# FPGA_POWER_DGND.net
KiCad netlist of a schematic drawn in Altium Designer
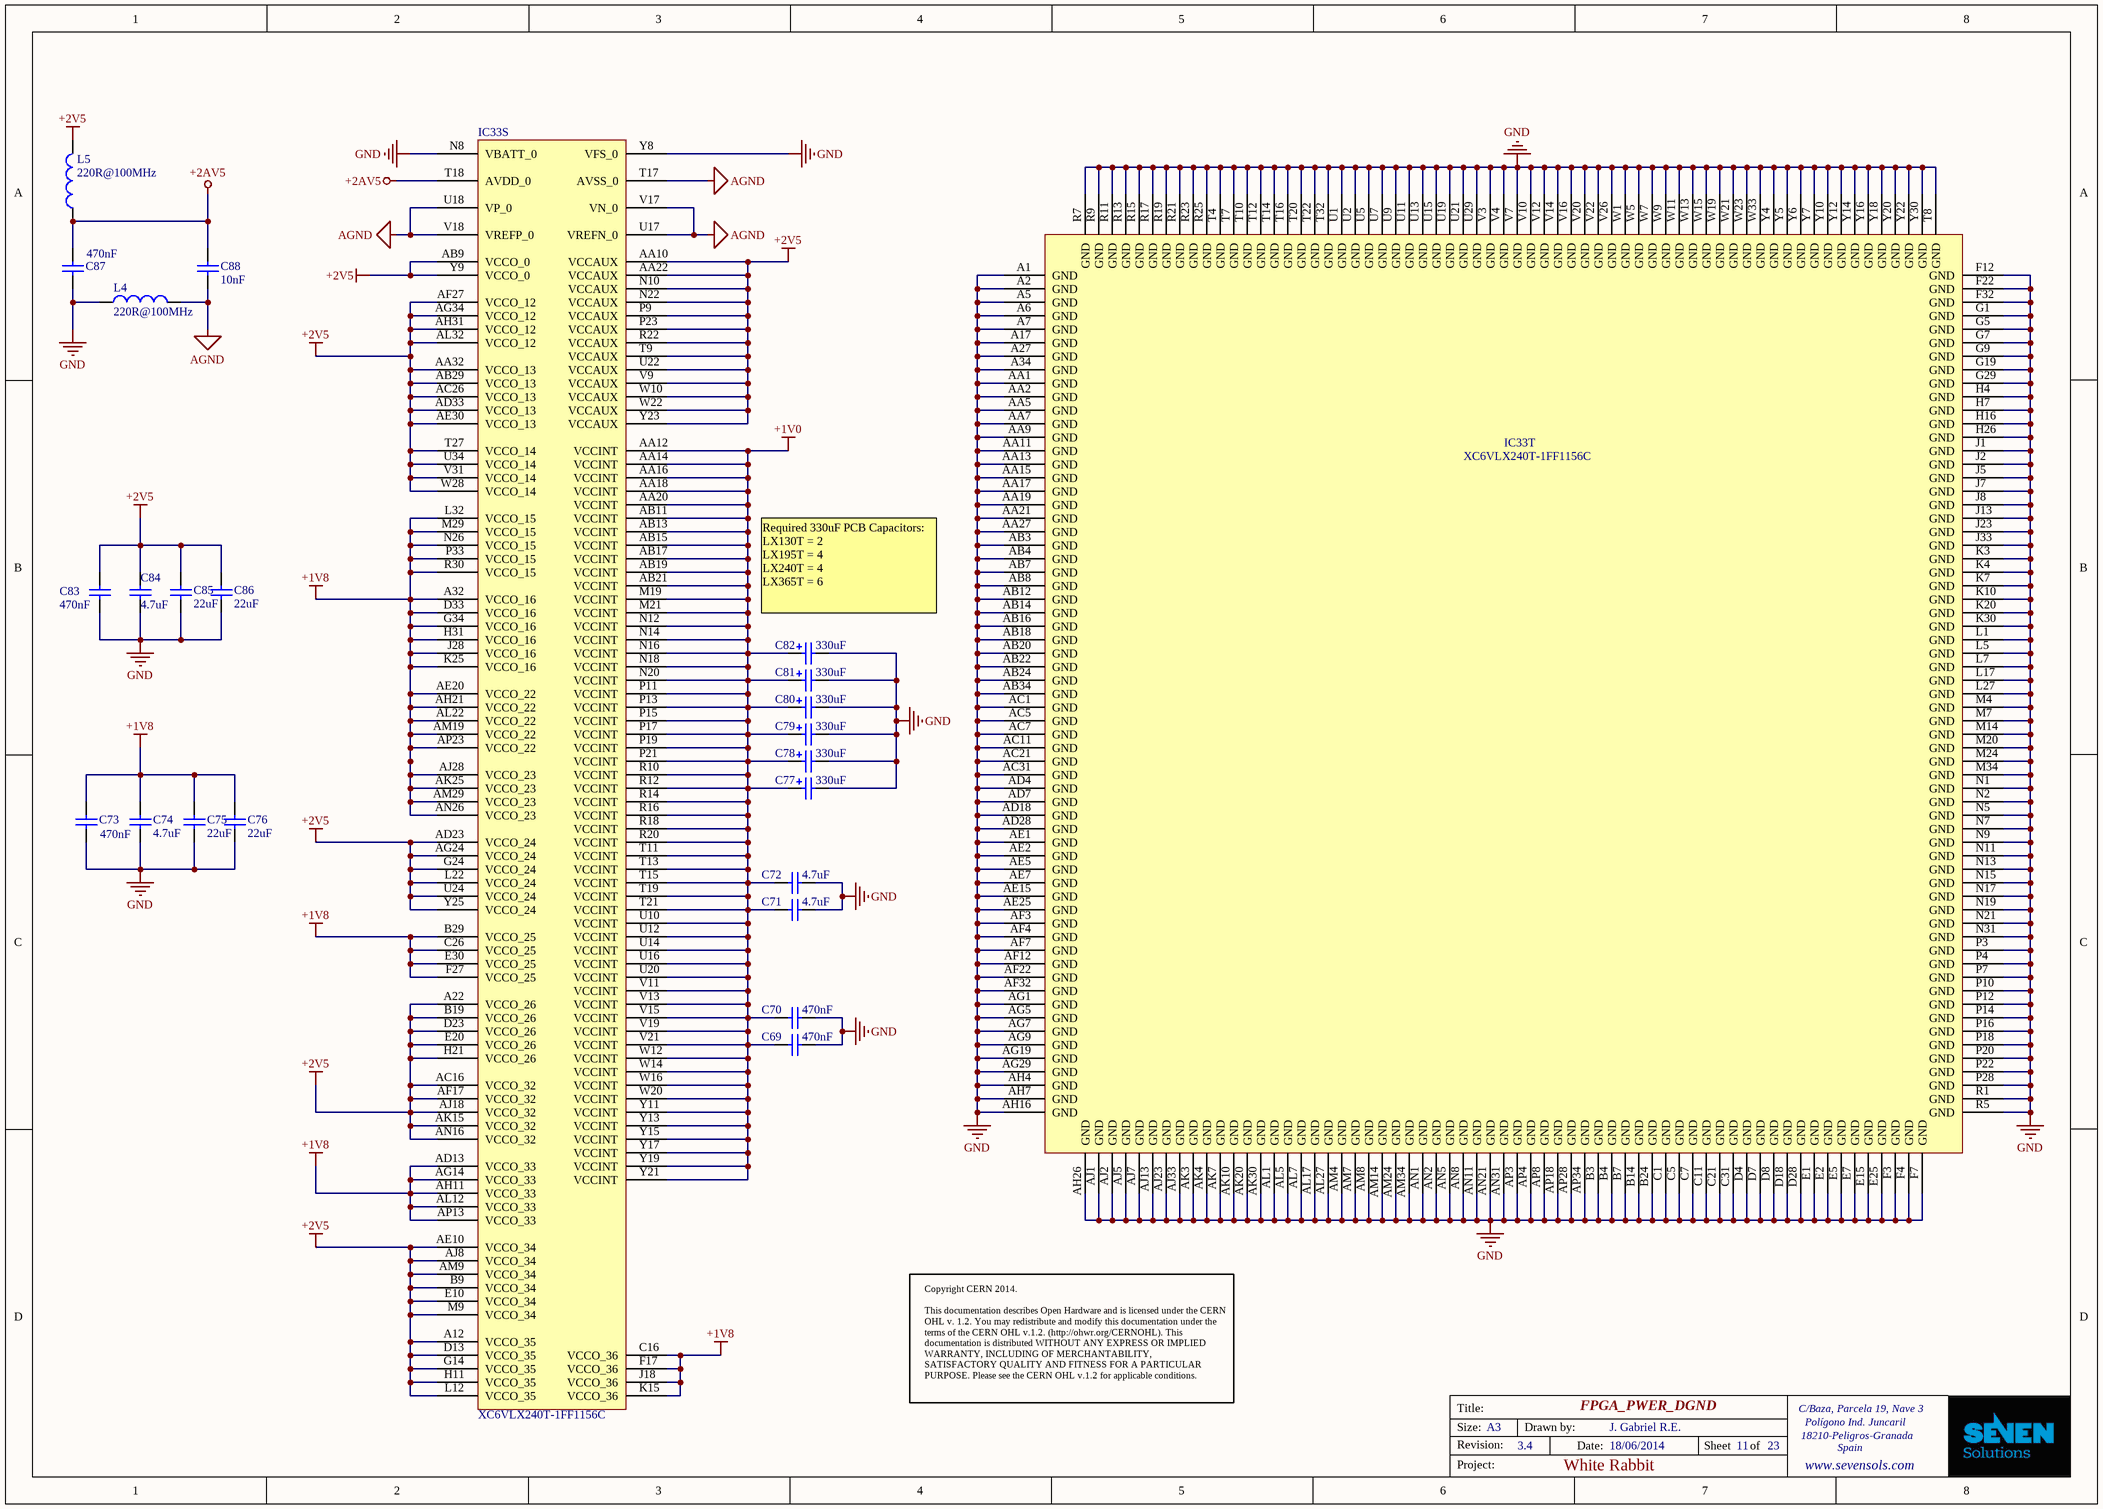
[diagram p0: FPGA_POWER_DGND.SchDoc]

(export (version "E")
  (design (tool "Eeschema 10.0.6"))
  (components
    (comp (ref "C69")
      (value "470nF")
      (footprint "CC1005-0402")
      (description "Capacitor")
      (fields
        (field (name "TOLERANCE") "±10%")
        (field (name "VOLTAGE") "16V")
        (field (name "PUBLISHER") "Altium Limited")
      )
      (libsource (lib "wr_switch") (part "Cap"))
    )
    (comp (ref "C70")
      (value "470nF")
      (footprint "CC1005-0402")
      (description "Capacitor")
      (fields
        (field (name "TOLERANCE") "±10%")
        (field (name "VOLTAGE") "16V")
        (field (name "PUBLISHER") "Altium Limited")
      )
      (libsource (lib "wr_switch") (part "Cap"))
    )
    (comp (ref "C71")
      (value "4.7uF")
      (footprint "CC1608-0603")
      (description "Capacitor")
      (fields
        (field (name "TOLERANCE") "±10%")
        (field (name "VOLTAGE") "10V")
        (field (name "PUBLISHER") "Altium Limited")
      )
      (libsource (lib "wr_switch") (part "Cap"))
    )
    (comp (ref "C72")
      (value "4.7uF")
      (footprint "CC1608-0603")
      (description "Capacitor")
      (fields
        (field (name "TOLERANCE") "±10%")
        (field (name "VOLTAGE") "10V")
        (field (name "PUBLISHER") "Altium Limited")
      )
      (libsource (lib "wr_switch") (part "Cap"))
    )
    (comp (ref "C73")
      (value "470nF")
      (footprint "CC1005-0402")
      (description "Capacitor")
      (fields
        (field (name "TOLERANCE") "±10%")
        (field (name "VOLTAGE") "16V")
        (field (name "PUBLISHER") "Altium Limited")
      )
      (libsource (lib "wr_switch") (part "Cap"))
    )
    (comp (ref "C74")
      (value "4.7uF")
      (footprint "CC1608-0603")
      (description "Capacitor")
      (fields
        (field (name "TOLERANCE") "±10%")
        (field (name "VOLTAGE") "10V")
        (field (name "PUBLISHER") "Altium Limited")
      )
      (libsource (lib "wr_switch") (part "Cap"))
    )
    (comp (ref "C75")
      (value "22uF")
      (footprint "CC2012-0805")
      (description "Capacitor")
      (fields
        (field (name "TOLERANCE") "±20%")
        (field (name "VOLTAGE") "6.3V")
        (field (name "PUBLISHER") "Altium Limited")
      )
      (libsource (lib "wr_switch") (part "Cap"))
    )
    (comp (ref "C76")
      (value "22uF")
      (footprint "CC2012-0805")
      (description "Capacitor")
      (fields
        (field (name "TOLERANCE") "±20%")
        (field (name "VOLTAGE") "6.3V")
        (field (name "PUBLISHER") "Altium Limited")
      )
      (libsource (lib "wr_switch") (part "Cap"))
    )
    (comp (ref "C77")
      (value "330uF")
      (footprint "D")
      (description "Polarized Capacitor Tantalum")
      (fields
        (field (name "TOLERANCE") "±20%")
        (field (name "VOLTAGE") "6.3V")
        (field (name "PUBLISHER") "Altium Limited")
      )
      (libsource (lib "wr_switch") (part "Cap Pol1"))
    )
    (comp (ref "C78")
      (value "330uF")
      (footprint "D")
      (description "Polarized Capacitor Tantalum")
      (fields
        (field (name "TOLERANCE") "±20%")
        (field (name "VOLTAGE") "6.3V")
        (field (name "PUBLISHER") "Altium Limited")
      )
      (libsource (lib "wr_switch") (part "Cap Pol1"))
    )
    (comp (ref "C79")
      (value "330uF")
      (footprint "D")
      (description "Polarized Capacitor Tantalum")
      (fields
        (field (name "TOLERANCE") "±20%")
        (field (name "VOLTAGE") "6.3V")
        (field (name "PUBLISHER") "Altium Limited")
      )
      (libsource (lib "wr_switch") (part "Cap Pol1"))
    )
    (comp (ref "C80")
      (value "330uF")
      (footprint "D")
      (description "Polarized Capacitor Tantalum")
      (fields
        (field (name "TOLERANCE") "±20%")
        (field (name "VOLTAGE") "6.3V")
        (field (name "PUBLISHER") "Altium Limited")
      )
      (libsource (lib "wr_switch") (part "Cap Pol1"))
    )
    (comp (ref "C81")
      (value "330uF")
      (footprint "D")
      (description "Polarized Capacitor Tantalum")
      (fields
        (field (name "TOLERANCE") "±20%")
        (field (name "VOLTAGE") "6.3V")
        (field (name "PUBLISHER") "Altium Limited")
      )
      (libsource (lib "wr_switch") (part "Cap Pol1"))
    )
    (comp (ref "C82")
      (value "330uF")
      (footprint "D")
      (description "Polarized Capacitor Tantalum")
      (fields
        (field (name "TOLERANCE") "±20%")
        (field (name "VOLTAGE") "6.3V")
        (field (name "PUBLISHER") "Altium Limited")
      )
      (libsource (lib "wr_switch") (part "Cap Pol1"))
    )
    (comp (ref "C83")
      (value "470nF")
      (footprint "CC1005-0402")
      (description "Capacitor")
      (fields
        (field (name "TOLERANCE") "±10%")
        (field (name "VOLTAGE") "16V")
        (field (name "PUBLISHER") "Altium Limited")
      )
      (libsource (lib "wr_switch") (part "Cap"))
    )
    (comp (ref "C84")
      (value "4.7uF")
      (footprint "CC1608-0603")
      (description "Capacitor")
      (fields
        (field (name "TOLERANCE") "±10%")
        (field (name "VOLTAGE") "10V")
        (field (name "PUBLISHER") "Altium Limited")
      )
      (libsource (lib "wr_switch") (part "Cap"))
    )
    (comp (ref "C85")
      (value "22uF")
      (footprint "CC2012-0805")
      (description "Capacitor")
      (fields
        (field (name "TOLERANCE") "±20%")
        (field (name "VOLTAGE") "6.3V")
        (field (name "PUBLISHER") "Altium Limited")
      )
      (libsource (lib "wr_switch") (part "Cap"))
    )
    (comp (ref "C86")
      (value "22uF")
      (footprint "CC2012-0805")
      (description "Capacitor")
      (fields
        (field (name "TOLERANCE") "±20%")
        (field (name "VOLTAGE") "6.3V")
        (field (name "PUBLISHER") "Altium Limited")
      )
      (libsource (lib "wr_switch") (part "Cap"))
    )
    (comp (ref "C87")
      (value "470nF")
      (footprint "CC1005-0402")
      (description "Capacitor")
      (fields
        (field (name "TOLERANCE") "±10%")
        (field (name "VOLTAGE") "16V")
        (field (name "PUBLISHER") "Altium Limited")
      )
      (libsource (lib "wr_switch") (part "Cap"))
    )
    (comp (ref "C88")
      (value "10nF")
      (footprint "CC1005-0402")
      (description "Capacitor")
      (fields
        (field (name "TOLERANCE") "±10%")
        (field (name "VOLTAGE") "25V")
        (field (name "PUBLISHER") "Altium Limited")
      )
      (libsource (lib "wr_switch") (part "Cap"))
    )
    (comp (ref "IC33")
      (value "XC6VLX240T-1FF1156C")
      (footprint "FF1156")
      (fields (field (name "PUBLISHER") "Altium Limited"))
      (libsource (lib "Xilinx Virtex-6") (part "XC6VLX240T-1FF1156C"))
    )
    (comp (ref "L4")
      (value "220R@100MHz Ferrite Bead")
      (footprint "0603")
      (description "ferrite bead")
      (fields (field (name "IMPEDANCE") "220R@100MHz"))
      (libsource (lib "wr_switch") (part "L_FERRITE_BEAD"))
    )
    (comp (ref "L5")
      (value "220R@100MHz Ferrite Bead")
      (footprint "0603")
      (description "ferrite bead")
      (fields (field (name "IMPEDANCE") "220R@100MHz"))
      (libsource (lib "wr_switch") (part "L_FERRITE_BEAD"))
    )
  )
  (nets
    (net (code "1") (name "+1V0") (class "Default")
      (node (ref "C69") (pin "2") (pinfunction "2_2") (pintype "passive"))
      (node (ref "C70") (pin "2") (pinfunction "2_2") (pintype "passive"))
      (node (ref "C71") (pin "1") (pinfunction "1_1") (pintype "passive"))
      (node (ref "C72") (pin "1") (pinfunction "1_1") (pintype "passive"))
      (node (ref "C77") (pin "1") (pinfunction "1_1") (pintype "passive"))
      (node (ref "C78") (pin "1") (pinfunction "1_1") (pintype "passive"))
      (node (ref "C79") (pin "1") (pinfunction "1_1") (pintype "passive"))
      (node (ref "C80") (pin "1") (pinfunction "1_1") (pintype "passive"))
      (node (ref "C81") (pin "1") (pinfunction "1_1") (pintype "passive"))
      (node (ref "C82") (pin "1") (pinfunction "1_1") (pintype "passive"))
      (node (ref "IC33") (pin "AA12") (pinfunction "VCCINT_AA12") (pintype "power_in"))
      (node (ref "IC33") (pin "AA14") (pinfunction "VCCINT_AA14") (pintype "power_in"))
      (node (ref "IC33") (pin "AA16") (pinfunction "VCCINT_AA16") (pintype "power_in"))
      (node (ref "IC33") (pin "AA18") (pinfunction "VCCINT_AA18") (pintype "power_in"))
      (node (ref "IC33") (pin "AA20") (pinfunction "VCCINT_AA20") (pintype "power_in"))
      (node (ref "IC33") (pin "AB11") (pinfunction "VCCINT_AB11") (pintype "power_in"))
      (node (ref "IC33") (pin "AB13") (pinfunction "VCCINT_AB13") (pintype "power_in"))
      (node (ref "IC33") (pin "AB15") (pinfunction "VCCINT_AB15") (pintype "power_in"))
      (node (ref "IC33") (pin "AB17") (pinfunction "VCCINT_AB17") (pintype "power_in"))
      (node (ref "IC33") (pin "AB19") (pinfunction "VCCINT_AB19") (pintype "power_in"))
      (node (ref "IC33") (pin "AB21") (pinfunction "VCCINT_AB21") (pintype "power_in"))
      (node (ref "IC33") (pin "M19") (pinfunction "VCCINT_M19") (pintype "power_in"))
      (node (ref "IC33") (pin "M21") (pinfunction "VCCINT_M21") (pintype "power_in"))
      (node (ref "IC33") (pin "N12") (pinfunction "VCCINT_N12") (pintype "power_in"))
      (node (ref "IC33") (pin "N14") (pinfunction "VCCINT_N14") (pintype "power_in"))
      (node (ref "IC33") (pin "N16") (pinfunction "VCCINT_N16") (pintype "power_in"))
      (node (ref "IC33") (pin "N18") (pinfunction "VCCINT_N18") (pintype "power_in"))
      (node (ref "IC33") (pin "N20") (pinfunction "VCCINT_N20") (pintype "power_in"))
      (node (ref "IC33") (pin "P11") (pinfunction "VCCINT_P11") (pintype "power_in"))
      (node (ref "IC33") (pin "P13") (pinfunction "VCCINT_P13") (pintype "power_in"))
      (node (ref "IC33") (pin "P15") (pinfunction "VCCINT_P15") (pintype "power_in"))
      (node (ref "IC33") (pin "P17") (pinfunction "VCCINT_P17") (pintype "power_in"))
      (node (ref "IC33") (pin "P19") (pinfunction "VCCINT_P19") (pintype "power_in"))
      (node (ref "IC33") (pin "P21") (pinfunction "VCCINT_P21") (pintype "power_in"))
      (node (ref "IC33") (pin "R10") (pinfunction "VCCINT_R10") (pintype "power_in"))
      (node (ref "IC33") (pin "R12") (pinfunction "VCCINT_R12") (pintype "power_in"))
      (node (ref "IC33") (pin "R14") (pinfunction "VCCINT_R14") (pintype "power_in"))
      (node (ref "IC33") (pin "R16") (pinfunction "VCCINT_R16") (pintype "power_in"))
      (node (ref "IC33") (pin "R18") (pinfunction "VCCINT_R18") (pintype "power_in"))
      (node (ref "IC33") (pin "R20") (pinfunction "VCCINT_R20") (pintype "power_in"))
      (node (ref "IC33") (pin "T11") (pinfunction "VCCINT_T11") (pintype "power_in"))
      (node (ref "IC33") (pin "T13") (pinfunction "VCCINT_T13") (pintype "power_in"))
      (node (ref "IC33") (pin "T15") (pinfunction "VCCINT_T15") (pintype "power_in"))
      (node (ref "IC33") (pin "T19") (pinfunction "VCCINT_T19") (pintype "power_in"))
      (node (ref "IC33") (pin "T21") (pinfunction "VCCINT_T21") (pintype "power_in"))
      (node (ref "IC33") (pin "U10") (pinfunction "VCCINT_U10") (pintype "power_in"))
      (node (ref "IC33") (pin "U12") (pinfunction "VCCINT_U12") (pintype "power_in"))
      (node (ref "IC33") (pin "U14") (pinfunction "VCCINT_U14") (pintype "power_in"))
      (node (ref "IC33") (pin "U16") (pinfunction "VCCINT_U16") (pintype "power_in"))
      (node (ref "IC33") (pin "U20") (pinfunction "VCCINT_U20") (pintype "power_in"))
      (node (ref "IC33") (pin "V11") (pinfunction "VCCINT_V11") (pintype "power_in"))
      (node (ref "IC33") (pin "V13") (pinfunction "VCCINT_V13") (pintype "power_in"))
      (node (ref "IC33") (pin "V15") (pinfunction "VCCINT_V15") (pintype "power_in"))
      (node (ref "IC33") (pin "V19") (pinfunction "VCCINT_V19") (pintype "power_in"))
      (node (ref "IC33") (pin "V21") (pinfunction "VCCINT_V21") (pintype "power_in"))
      (node (ref "IC33") (pin "W12") (pinfunction "VCCINT_W12") (pintype "power_in"))
      (node (ref "IC33") (pin "W14") (pinfunction "VCCINT_W14") (pintype "power_in"))
      (node (ref "IC33") (pin "W16") (pinfunction "VCCINT_W16") (pintype "power_in"))
      (node (ref "IC33") (pin "W20") (pinfunction "VCCINT_W20") (pintype "power_in"))
      (node (ref "IC33") (pin "Y11") (pinfunction "VCCINT_Y11") (pintype "power_in"))
      (node (ref "IC33") (pin "Y13") (pinfunction "VCCINT_Y13") (pintype "power_in"))
      (node (ref "IC33") (pin "Y15") (pinfunction "VCCINT_Y15") (pintype "power_in"))
      (node (ref "IC33") (pin "Y17") (pinfunction "VCCINT_Y17") (pintype "power_in"))
      (node (ref "IC33") (pin "Y19") (pinfunction "VCCINT_Y19") (pintype "power_in"))
      (node (ref "IC33") (pin "Y21") (pinfunction "VCCINT_Y21") (pintype "power_in"))
    )
    (net (code "2") (name "+1V8") (class "Default")
      (node (ref "C73") (pin "1") (pinfunction "1_1") (pintype "passive"))
      (node (ref "C74") (pin "2") (pinfunction "2_2") (pintype "passive"))
      (node (ref "C75") (pin "2") (pinfunction "2_2") (pintype "passive"))
      (node (ref "C76") (pin "2") (pinfunction "2_2") (pintype "passive"))
      (node (ref "IC33") (pin "A32") (pinfunction "VCCO_16_A32") (pintype "power_in"))
      (node (ref "IC33") (pin "AD13") (pinfunction "VCCO_33_AD13") (pintype "power_in"))
      (node (ref "IC33") (pin "AE20") (pinfunction "VCCO_22_AE20") (pintype "power_in"))
      (node (ref "IC33") (pin "AG14") (pinfunction "VCCO_33_AG14") (pintype "power_in"))
      (node (ref "IC33") (pin "AH11") (pinfunction "VCCO_33_AH11") (pintype "power_in"))
      (node (ref "IC33") (pin "AH21") (pinfunction "VCCO_22_AH21") (pintype "power_in"))
      (node (ref "IC33") (pin "AJ28") (pinfunction "VCCO_23_AJ28") (pintype "power_in"))
      (node (ref "IC33") (pin "AK25") (pinfunction "VCCO_23_AK25") (pintype "power_in"))
      (node (ref "IC33") (pin "AL12") (pinfunction "VCCO_33_AL12") (pintype "power_in"))
      (node (ref "IC33") (pin "AL22") (pinfunction "VCCO_22_AL22") (pintype "power_in"))
      (node (ref "IC33") (pin "AM19") (pinfunction "VCCO_22_AM19") (pintype "power_in"))
      (node (ref "IC33") (pin "AM29") (pinfunction "VCCO_23_AM29") (pintype "power_in"))
      (node (ref "IC33") (pin "AN26") (pinfunction "VCCO_23_AN26") (pintype "power_in"))
      (node (ref "IC33") (pin "AP13") (pinfunction "VCCO_33_AP13") (pintype "power_in"))
      (node (ref "IC33") (pin "AP23") (pinfunction "VCCO_22_AP23") (pintype "power_in"))
      (node (ref "IC33") (pin "B29") (pinfunction "VCCO_25_B29") (pintype "power_in"))
      (node (ref "IC33") (pin "C16") (pinfunction "VCCO_36_C16") (pintype "power_in"))
      (node (ref "IC33") (pin "C26") (pinfunction "VCCO_25_C26") (pintype "power_in"))
      (node (ref "IC33") (pin "D33") (pinfunction "VCCO_16_D33") (pintype "power_in"))
      (node (ref "IC33") (pin "E30") (pinfunction "VCCO_25_E30") (pintype "power_in"))
      (node (ref "IC33") (pin "F17") (pinfunction "VCCO_36_F17") (pintype "power_in"))
      (node (ref "IC33") (pin "F27") (pinfunction "VCCO_25_F27") (pintype "power_in"))
      (node (ref "IC33") (pin "G34") (pinfunction "VCCO_16_G34") (pintype "power_in"))
      (node (ref "IC33") (pin "H31") (pinfunction "VCCO_16_H31") (pintype "power_in"))
      (node (ref "IC33") (pin "J18") (pinfunction "VCCO_36_J18") (pintype "power_in"))
      (node (ref "IC33") (pin "J28") (pinfunction "VCCO_16_J28") (pintype "power_in"))
      (node (ref "IC33") (pin "K15") (pinfunction "VCCO_36_K15") (pintype "power_in"))
      (node (ref "IC33") (pin "K25") (pinfunction "VCCO_16_K25") (pintype "power_in"))
      (node (ref "IC33") (pin "L32") (pinfunction "VCCO_15_L32") (pintype "power_in"))
      (node (ref "IC33") (pin "M29") (pinfunction "VCCO_15_M29") (pintype "power_in"))
      (node (ref "IC33") (pin "N26") (pinfunction "VCCO_15_N26") (pintype "power_in"))
      (node (ref "IC33") (pin "P33") (pinfunction "VCCO_15_P33") (pintype "power_in"))
      (node (ref "IC33") (pin "R30") (pinfunction "VCCO_15_R30") (pintype "power_in"))
    )
    (net (code "3") (name "+2AV5") (class "Default")
      (node (ref "C87") (pin "1") (pinfunction "1_1") (pintype "passive"))
      (node (ref "C88") (pin "1") (pinfunction "1_1") (pintype "passive"))
      (node (ref "IC33") (pin "T18") (pinfunction "AVDD_0_T18") (pintype "power_in"))
      (node (ref "L5") (pin "1") (pinfunction "1_1") (pintype "passive"))
    )
    (net (code "4") (name "+2V5") (class "Default")
      (node (ref "C83") (pin "1") (pinfunction "1_1") (pintype "passive"))
      (node (ref "C84") (pin "2") (pinfunction "2_2") (pintype "passive"))
      (node (ref "C85") (pin "2") (pinfunction "2_2") (pintype "passive"))
      (node (ref "C86") (pin "2") (pinfunction "2_2") (pintype "passive"))
      (node (ref "IC33") (pin "A12") (pinfunction "VCCO_35_A12") (pintype "power_in"))
      (node (ref "IC33") (pin "A22") (pinfunction "VCCO_26_A22") (pintype "power_in"))
      (node (ref "IC33") (pin "AA10") (pinfunction "VCCAUX_AA10") (pintype "power_in"))
      (node (ref "IC33") (pin "AA22") (pinfunction "VCCAUX_AA22") (pintype "power_in"))
      (node (ref "IC33") (pin "AA32") (pinfunction "VCCO_13_AA32") (pintype "power_in"))
      (node (ref "IC33") (pin "AB29") (pinfunction "VCCO_13_AB29") (pintype "power_in"))
      (node (ref "IC33") (pin "AB9") (pinfunction "VCCO_0_AB9") (pintype "power_in"))
      (node (ref "IC33") (pin "AC16") (pinfunction "VCCO_32_AC16") (pintype "power_in"))
      (node (ref "IC33") (pin "AC26") (pinfunction "VCCO_13_AC26") (pintype "power_in"))
      (node (ref "IC33") (pin "AD23") (pinfunction "VCCO_24_AD23") (pintype "power_in"))
      (node (ref "IC33") (pin "AD33") (pinfunction "VCCO_13_AD33") (pintype "power_in"))
      (node (ref "IC33") (pin "AE10") (pinfunction "VCCO_34_AE10") (pintype "power_in"))
      (node (ref "IC33") (pin "AE30") (pinfunction "VCCO_13_AE30") (pintype "power_in"))
      (node (ref "IC33") (pin "AF17") (pinfunction "VCCO_32_AF17") (pintype "power_in"))
      (node (ref "IC33") (pin "AF27") (pinfunction "VCCO_12_AF27") (pintype "power_in"))
      (node (ref "IC33") (pin "AG24") (pinfunction "VCCO_24_AG24") (pintype "power_in"))
      (node (ref "IC33") (pin "AG34") (pinfunction "VCCO_12_AG34") (pintype "power_in"))
      (node (ref "IC33") (pin "AH31") (pinfunction "VCCO_12_AH31") (pintype "power_in"))
      (node (ref "IC33") (pin "AJ18") (pinfunction "VCCO_32_AJ18") (pintype "power_in"))
      (node (ref "IC33") (pin "AJ8") (pinfunction "VCCO_34_AJ8") (pintype "power_in"))
      (node (ref "IC33") (pin "AK15") (pinfunction "VCCO_32_AK15") (pintype "power_in"))
      (node (ref "IC33") (pin "AL32") (pinfunction "VCCO_12_AL32") (pintype "power_in"))
      (node (ref "IC33") (pin "AM9") (pinfunction "VCCO_34_AM9") (pintype "power_in"))
      (node (ref "IC33") (pin "AN16") (pinfunction "VCCO_32_AN16") (pintype "power_in"))
      (node (ref "IC33") (pin "B19") (pinfunction "VCCO_26_B19") (pintype "power_in"))
      (node (ref "IC33") (pin "B9") (pinfunction "VCCO_34_B9") (pintype "power_in"))
      (node (ref "IC33") (pin "D13") (pinfunction "VCCO_35_D13") (pintype "power_in"))
      (node (ref "IC33") (pin "D23") (pinfunction "VCCO_26_D23") (pintype "power_in"))
      (node (ref "IC33") (pin "E10") (pinfunction "VCCO_34_E10") (pintype "power_in"))
      (node (ref "IC33") (pin "E20") (pinfunction "VCCO_26_E20") (pintype "power_in"))
      (node (ref "IC33") (pin "G14") (pinfunction "VCCO_35_G14") (pintype "power_in"))
      (node (ref "IC33") (pin "G24") (pinfunction "VCCO_24_G24") (pintype "power_in"))
      (node (ref "IC33") (pin "H11") (pinfunction "VCCO_35_H11") (pintype "power_in"))
      (node (ref "IC33") (pin "H21") (pinfunction "VCCO_26_H21") (pintype "power_in"))
      (node (ref "IC33") (pin "L12") (pinfunction "VCCO_35_L12") (pintype "power_in"))
      (node (ref "IC33") (pin "L22") (pinfunction "VCCO_24_L22") (pintype "power_in"))
      (node (ref "IC33") (pin "M9") (pinfunction "VCCO_34_M9") (pintype "power_in"))
      (node (ref "IC33") (pin "N10") (pinfunction "VCCAUX_N10") (pintype "power_in"))
      (node (ref "IC33") (pin "N22") (pinfunction "VCCAUX_N22") (pintype "power_in"))
      (node (ref "IC33") (pin "P23") (pinfunction "VCCAUX_P23") (pintype "power_in"))
      (node (ref "IC33") (pin "P9") (pinfunction "VCCAUX_P9") (pintype "power_in"))
      (node (ref "IC33") (pin "R22") (pinfunction "VCCAUX_R22") (pintype "power_in"))
      (node (ref "IC33") (pin "T27") (pinfunction "VCCO_14_T27") (pintype "power_in"))
      (node (ref "IC33") (pin "T9") (pinfunction "VCCAUX_T9") (pintype "power_in"))
      (node (ref "IC33") (pin "U22") (pinfunction "VCCAUX_U22") (pintype "power_in"))
      (node (ref "IC33") (pin "U24") (pinfunction "VCCO_24_U24") (pintype "power_in"))
      (node (ref "IC33") (pin "U34") (pinfunction "VCCO_14_U34") (pintype "power_in"))
      (node (ref "IC33") (pin "V31") (pinfunction "VCCO_14_V31") (pintype "power_in"))
      (node (ref "IC33") (pin "V9") (pinfunction "VCCAUX_V9") (pintype "power_in"))
      (node (ref "IC33") (pin "W10") (pinfunction "VCCAUX_W10") (pintype "power_in"))
      (node (ref "IC33") (pin "W22") (pinfunction "VCCAUX_W22") (pintype "power_in"))
      (node (ref "IC33") (pin "W28") (pinfunction "VCCO_14_W28") (pintype "power_in"))
      (node (ref "IC33") (pin "Y23") (pinfunction "VCCAUX_Y23") (pintype "power_in"))
      (node (ref "IC33") (pin "Y25") (pinfunction "VCCO_24_Y25") (pintype "power_in"))
      (node (ref "IC33") (pin "Y9") (pinfunction "VCCO_0_Y9") (pintype "power_in"))
      (node (ref "L5") (pin "2") (pinfunction "2_2") (pintype "passive"))
    )
    (net (code "5") (name "AGND") (class "Default")
      (node (ref "C88") (pin "2") (pinfunction "2_2") (pintype "passive"))
      (node (ref "IC33") (pin "T17") (pinfunction "AVSS_0_T17") (pintype "power_in"))
      (node (ref "IC33") (pin "U17") (pinfunction "VREFN_0_U17") (pintype "power_in"))
      (node (ref "IC33") (pin "U18") (pinfunction "VP_0_U18") (pintype "power_in"))
      (node (ref "IC33") (pin "V17") (pinfunction "VN_0_V17") (pintype "power_in"))
      (node (ref "IC33") (pin "V18") (pinfunction "VREFP_0_V18") (pintype "power_in"))
      (node (ref "L4") (pin "2") (pinfunction "2_2") (pintype "passive"))
    )
    (net (code "6") (name "GND") (class "Default")
      (node (ref "C69") (pin "1") (pinfunction "1_1") (pintype "passive"))
      (node (ref "C70") (pin "1") (pinfunction "1_1") (pintype "passive"))
      (node (ref "C71") (pin "2") (pinfunction "2_2") (pintype "passive"))
      (node (ref "C72") (pin "2") (pinfunction "2_2") (pintype "passive"))
      (node (ref "C73") (pin "2") (pinfunction "2_2") (pintype "passive"))
      (node (ref "C74") (pin "1") (pinfunction "1_1") (pintype "passive"))
      (node (ref "C75") (pin "1") (pinfunction "1_1") (pintype "passive"))
      (node (ref "C76") (pin "1") (pinfunction "1_1") (pintype "passive"))
      (node (ref "C77") (pin "2") (pinfunction "2_2") (pintype "passive"))
      (node (ref "C78") (pin "2") (pinfunction "2_2") (pintype "passive"))
      (node (ref "C79") (pin "2") (pinfunction "2_2") (pintype "passive"))
      (node (ref "C80") (pin "2") (pinfunction "2_2") (pintype "passive"))
      (node (ref "C81") (pin "2") (pinfunction "2_2") (pintype "passive"))
      (node (ref "C82") (pin "2") (pinfunction "2_2") (pintype "passive"))
      (node (ref "C83") (pin "2") (pinfunction "2_2") (pintype "passive"))
      (node (ref "C84") (pin "1") (pinfunction "1_1") (pintype "passive"))
      (node (ref "C85") (pin "1") (pinfunction "1_1") (pintype "passive"))
      (node (ref "C86") (pin "1") (pinfunction "1_1") (pintype "passive"))
      (node (ref "C87") (pin "2") (pinfunction "2_2") (pintype "passive"))
      (node (ref "IC33") (pin "A1") (pinfunction "GND_A1") (pintype "power_in"))
      (node (ref "IC33") (pin "A17") (pinfunction "GND_A17") (pintype "power_in"))
      (node (ref "IC33") (pin "A2") (pinfunction "GND_A2") (pintype "power_in"))
      (node (ref "IC33") (pin "A27") (pinfunction "GND_A27") (pintype "power_in"))
      (node (ref "IC33") (pin "A34") (pinfunction "GND_A34") (pintype "power_in"))
      (node (ref "IC33") (pin "A5") (pinfunction "GND_A5") (pintype "power_in"))
      (node (ref "IC33") (pin "A6") (pinfunction "GND_A6") (pintype "power_in"))
      (node (ref "IC33") (pin "A7") (pinfunction "GND_A7") (pintype "power_in"))
      (node (ref "IC33") (pin "AA1") (pinfunction "GND_AA1") (pintype "power_in"))
      (node (ref "IC33") (pin "AA11") (pinfunction "GND_AA11") (pintype "power_in"))
      (node (ref "IC33") (pin "AA13") (pinfunction "GND_AA13") (pintype "power_in"))
      (node (ref "IC33") (pin "AA15") (pinfunction "GND_AA15") (pintype "power_in"))
      (node (ref "IC33") (pin "AA17") (pinfunction "GND_AA17") (pintype "power_in"))
      (node (ref "IC33") (pin "AA19") (pinfunction "GND_AA19") (pintype "power_in"))
      (node (ref "IC33") (pin "AA2") (pinfunction "GND_AA2") (pintype "power_in"))
      (node (ref "IC33") (pin "AA21") (pinfunction "GND_AA21") (pintype "power_in"))
      (node (ref "IC33") (pin "AA27") (pinfunction "GND_AA27") (pintype "power_in"))
      (node (ref "IC33") (pin "AA5") (pinfunction "GND_AA5") (pintype "power_in"))
      (node (ref "IC33") (pin "AA7") (pinfunction "GND_AA7") (pintype "power_in"))
      (node (ref "IC33") (pin "AA9") (pinfunction "GND_AA9") (pintype "power_in"))
      (node (ref "IC33") (pin "AB12") (pinfunction "GND_AB12") (pintype "power_in"))
      (node (ref "IC33") (pin "AB14") (pinfunction "GND_AB14") (pintype "power_in"))
      (node (ref "IC33") (pin "AB16") (pinfunction "GND_AB16") (pintype "power_in"))
      (node (ref "IC33") (pin "AB18") (pinfunction "GND_AB18") (pintype "power_in"))
      (node (ref "IC33") (pin "AB20") (pinfunction "GND_AB20") (pintype "power_in"))
      (node (ref "IC33") (pin "AB22") (pinfunction "GND_AB22") (pintype "power_in"))
      (node (ref "IC33") (pin "AB24") (pinfunction "GND_AB24") (pintype "power_in"))
      (node (ref "IC33") (pin "AB3") (pinfunction "GND_AB3") (pintype "power_in"))
      (node (ref "IC33") (pin "AB34") (pinfunction "GND_AB34") (pintype "power_in"))
      (node (ref "IC33") (pin "AB4") (pinfunction "GND_AB4") (pintype "power_in"))
      (node (ref "IC33") (pin "AB7") (pinfunction "GND_AB7") (pintype "power_in"))
      (node (ref "IC33") (pin "AB8") (pinfunction "GND_AB8") (pintype "power_in"))
      (node (ref "IC33") (pin "AC1") (pinfunction "GND_AC1") (pintype "power_in"))
      (node (ref "IC33") (pin "AC11") (pinfunction "GND_AC11") (pintype "power_in"))
      (node (ref "IC33") (pin "AC21") (pinfunction "GND_AC21") (pintype "power_in"))
      (node (ref "IC33") (pin "AC31") (pinfunction "GND_AC31") (pintype "power_in"))
      (node (ref "IC33") (pin "AC5") (pinfunction "GND_AC5") (pintype "power_in"))
      (node (ref "IC33") (pin "AC7") (pinfunction "GND_AC7") (pintype "power_in"))
      (node (ref "IC33") (pin "AD18") (pinfunction "GND_AD18") (pintype "power_in"))
      (node (ref "IC33") (pin "AD28") (pinfunction "GND_AD28") (pintype "power_in"))
      (node (ref "IC33") (pin "AD4") (pinfunction "GND_AD4") (pintype "power_in"))
      (node (ref "IC33") (pin "AD7") (pinfunction "GND_AD7") (pintype "power_in"))
      (node (ref "IC33") (pin "AE1") (pinfunction "GND_AE1") (pintype "power_in"))
      (node (ref "IC33") (pin "AE15") (pinfunction "GND_AE15") (pintype "power_in"))
      (node (ref "IC33") (pin "AE2") (pinfunction "GND_AE2") (pintype "power_in"))
      (node (ref "IC33") (pin "AE25") (pinfunction "GND_AE25") (pintype "power_in"))
      (node (ref "IC33") (pin "AE5") (pinfunction "GND_AE5") (pintype "power_in"))
      (node (ref "IC33") (pin "AE7") (pinfunction "GND_AE7") (pintype "power_in"))
      (node (ref "IC33") (pin "AF12") (pinfunction "GND_AF12") (pintype "power_in"))
      (node (ref "IC33") (pin "AF22") (pinfunction "GND_AF22") (pintype "power_in"))
      (node (ref "IC33") (pin "AF3") (pinfunction "GND_AF3") (pintype "power_in"))
      (node (ref "IC33") (pin "AF32") (pinfunction "GND_AF32") (pintype "power_in"))
      (node (ref "IC33") (pin "AF4") (pinfunction "GND_AF4") (pintype "power_in"))
      (node (ref "IC33") (pin "AF7") (pinfunction "GND_AF7") (pintype "power_in"))
      (node (ref "IC33") (pin "AG1") (pinfunction "GND_AG1") (pintype "power_in"))
      (node (ref "IC33") (pin "AG19") (pinfunction "GND_AG19") (pintype "power_in"))
      (node (ref "IC33") (pin "AG29") (pinfunction "GND_AG29") (pintype "power_in"))
      (node (ref "IC33") (pin "AG5") (pinfunction "GND_AG5") (pintype "power_in"))
      (node (ref "IC33") (pin "AG7") (pinfunction "GND_AG7") (pintype "power_in"))
      (node (ref "IC33") (pin "AG9") (pinfunction "GND_AG9") (pintype "power_in"))
      (node (ref "IC33") (pin "AH16") (pinfunction "GND_AH16") (pintype "power_in"))
      (node (ref "IC33") (pin "AH26") (pinfunction "GND_AH26") (pintype "power_in"))
      (node (ref "IC33") (pin "AH4") (pinfunction "GND_AH4") (pintype "power_in"))
      (node (ref "IC33") (pin "AH7") (pinfunction "GND_AH7") (pintype "power_in"))
      (node (ref "IC33") (pin "AJ1") (pinfunction "GND_AJ1") (pintype "power_in"))
      (node (ref "IC33") (pin "AJ13") (pinfunction "GND_AJ13") (pintype "power_in"))
      (node (ref "IC33") (pin "AJ2") (pinfunction "GND_AJ2") (pintype "power_in"))
      (node (ref "IC33") (pin "AJ23") (pinfunction "GND_AJ23") (pintype "power_in"))
      (node (ref "IC33") (pin "AJ33") (pinfunction "GND_AJ33") (pintype "power_in"))
      (node (ref "IC33") (pin "AJ5") (pinfunction "GND_AJ5") (pintype "power_in"))
      (node (ref "IC33") (pin "AJ7") (pinfunction "GND_AJ7") (pintype "power_in"))
      (node (ref "IC33") (pin "AK10") (pinfunction "GND_AK10") (pintype "power_in"))
      (node (ref "IC33") (pin "AK20") (pinfunction "GND_AK20") (pintype "power_in"))
      (node (ref "IC33") (pin "AK3") (pinfunction "GND_AK3") (pintype "power_in"))
      (node (ref "IC33") (pin "AK30") (pinfunction "GND_AK30") (pintype "power_in"))
      (node (ref "IC33") (pin "AK4") (pinfunction "GND_AK4") (pintype "power_in"))
      (node (ref "IC33") (pin "AK7") (pinfunction "GND_AK7") (pintype "power_in"))
      (node (ref "IC33") (pin "AL1") (pinfunction "GND_AL1") (pintype "power_in"))
      (node (ref "IC33") (pin "AL17") (pinfunction "GND_AL17") (pintype "power_in"))
      (node (ref "IC33") (pin "AL27") (pinfunction "GND_AL27") (pintype "power_in"))
      (node (ref "IC33") (pin "AL5") (pinfunction "GND_AL5") (pintype "power_in"))
      (node (ref "IC33") (pin "AL7") (pinfunction "GND_AL7") (pintype "power_in"))
      (node (ref "IC33") (pin "AM14") (pinfunction "GND_AM14") (pintype "power_in"))
      (node (ref "IC33") (pin "AM24") (pinfunction "GND_AM24") (pintype "power_in"))
      (node (ref "IC33") (pin "AM34") (pinfunction "GND_AM34") (pintype "power_in"))
      (node (ref "IC33") (pin "AM4") (pinfunction "GND_AM4") (pintype "power_in"))
      (node (ref "IC33") (pin "AM7") (pinfunction "GND_AM7") (pintype "power_in"))
      (node (ref "IC33") (pin "AM8") (pinfunction "GND_AM8") (pintype "power_in"))
      (node (ref "IC33") (pin "AN1") (pinfunction "GND_AN1") (pintype "power_in"))
      (node (ref "IC33") (pin "AN11") (pinfunction "GND_AN11") (pintype "power_in"))
      (node (ref "IC33") (pin "AN2") (pinfunction "GND_AN2") (pintype "power_in"))
      (node (ref "IC33") (pin "AN21") (pinfunction "GND_AN21") (pintype "power_in"))
      (node (ref "IC33") (pin "AN31") (pinfunction "GND_AN31") (pintype "power_in"))
      (node (ref "IC33") (pin "AN5") (pinfunction "GND_AN5") (pintype "power_in"))
      (node (ref "IC33") (pin "AN8") (pinfunction "GND_AN8") (pintype "power_in"))
      (node (ref "IC33") (pin "AP18") (pinfunction "GND_AP18") (pintype "power_in"))
      (node (ref "IC33") (pin "AP28") (pinfunction "GND_AP28") (pintype "power_in"))
      (node (ref "IC33") (pin "AP3") (pinfunction "GND_AP3") (pintype "power_in"))
      (node (ref "IC33") (pin "AP34") (pinfunction "GND_AP34") (pintype "power_in"))
      (node (ref "IC33") (pin "AP4") (pinfunction "GND_AP4") (pintype "power_in"))
      (node (ref "IC33") (pin "AP8") (pinfunction "GND_AP8") (pintype "power_in"))
      (node (ref "IC33") (pin "B14") (pinfunction "GND_B14") (pintype "power_in"))
      (node (ref "IC33") (pin "B24") (pinfunction "GND_B24") (pintype "power_in"))
      (node (ref "IC33") (pin "B3") (pinfunction "GND_B3") (pintype "power_in"))
      (node (ref "IC33") (pin "B4") (pinfunction "GND_B4") (pintype "power_in"))
      (node (ref "IC33") (pin "B7") (pinfunction "GND_B7") (pintype "power_in"))
      (node (ref "IC33") (pin "C1") (pinfunction "GND_C1") (pintype "power_in"))
      (node (ref "IC33") (pin "C11") (pinfunction "GND_C11") (pintype "power_in"))
      (node (ref "IC33") (pin "C21") (pinfunction "GND_C21") (pintype "power_in"))
      (node (ref "IC33") (pin "C31") (pinfunction "GND_C31") (pintype "power_in"))
      (node (ref "IC33") (pin "C5") (pinfunction "GND_C5") (pintype "power_in"))
      (node (ref "IC33") (pin "C7") (pinfunction "GND_C7") (pintype "power_in"))
      (node (ref "IC33") (pin "D18") (pinfunction "GND_D18") (pintype "power_in"))
      (node (ref "IC33") (pin "D28") (pinfunction "GND_D28") (pintype "power_in"))
      (node (ref "IC33") (pin "D4") (pinfunction "GND_D4") (pintype "power_in"))
      (node (ref "IC33") (pin "D7") (pinfunction "GND_D7") (pintype "power_in"))
      (node (ref "IC33") (pin "D8") (pinfunction "GND_D8") (pintype "power_in"))
      (node (ref "IC33") (pin "E1") (pinfunction "GND_E1") (pintype "power_in"))
      (node (ref "IC33") (pin "E15") (pinfunction "GND_E15") (pintype "power_in"))
      (node (ref "IC33") (pin "E2") (pinfunction "GND_E2") (pintype "power_in"))
      (node (ref "IC33") (pin "E25") (pinfunction "GND_E25") (pintype "power_in"))
      (node (ref "IC33") (pin "E5") (pinfunction "GND_E5") (pintype "power_in"))
      (node (ref "IC33") (pin "E7") (pinfunction "GND_E7") (pintype "power_in"))
      (node (ref "IC33") (pin "F12") (pinfunction "GND_F12") (pintype "power_in"))
      (node (ref "IC33") (pin "F22") (pinfunction "GND_F22") (pintype "power_in"))
      (node (ref "IC33") (pin "F3") (pinfunction "GND_F3") (pintype "power_in"))
      (node (ref "IC33") (pin "F32") (pinfunction "GND_F32") (pintype "power_in"))
      (node (ref "IC33") (pin "F4") (pinfunction "GND_F4") (pintype "power_in"))
      (node (ref "IC33") (pin "F7") (pinfunction "GND_F7") (pintype "power_in"))
      (node (ref "IC33") (pin "G1") (pinfunction "GND_G1") (pintype "power_in"))
      (node (ref "IC33") (pin "G19") (pinfunction "GND_G19") (pintype "power_in"))
      (node (ref "IC33") (pin "G29") (pinfunction "GND_G29") (pintype "power_in"))
      (node (ref "IC33") (pin "G5") (pinfunction "GND_G5") (pintype "power_in"))
      (node (ref "IC33") (pin "G7") (pinfunction "GND_G7") (pintype "power_in"))
      (node (ref "IC33") (pin "G9") (pinfunction "GND_G9") (pintype "power_in"))
      (node (ref "IC33") (pin "H16") (pinfunction "GND_H16") (pintype "power_in"))
      (node (ref "IC33") (pin "H26") (pinfunction "GND_H26") (pintype "power_in"))
      (node (ref "IC33") (pin "H4") (pinfunction "GND_H4") (pintype "power_in"))
      (node (ref "IC33") (pin "H7") (pinfunction "GND_H7") (pintype "power_in"))
      (node (ref "IC33") (pin "J1") (pinfunction "GND_J1") (pintype "power_in"))
      (node (ref "IC33") (pin "J13") (pinfunction "GND_J13") (pintype "power_in"))
      (node (ref "IC33") (pin "J2") (pinfunction "GND_J2") (pintype "power_in"))
      (node (ref "IC33") (pin "J23") (pinfunction "GND_J23") (pintype "power_in"))
      (node (ref "IC33") (pin "J33") (pinfunction "GND_J33") (pintype "power_in"))
      (node (ref "IC33") (pin "J5") (pinfunction "GND_J5") (pintype "power_in"))
      (node (ref "IC33") (pin "J7") (pinfunction "GND_J7") (pintype "power_in"))
      (node (ref "IC33") (pin "J8") (pinfunction "GND_J8") (pintype "power_in"))
      (node (ref "IC33") (pin "K10") (pinfunction "GND_K10") (pintype "power_in"))
      (node (ref "IC33") (pin "K20") (pinfunction "GND_K20") (pintype "power_in"))
      (node (ref "IC33") (pin "K3") (pinfunction "GND_K3") (pintype "power_in"))
      (node (ref "IC33") (pin "K30") (pinfunction "GND_K30") (pintype "power_in"))
      (node (ref "IC33") (pin "K4") (pinfunction "GND_K4") (pintype "power_in"))
      (node (ref "IC33") (pin "K7") (pinfunction "GND_K7") (pintype "power_in"))
      (node (ref "IC33") (pin "L1") (pinfunction "GND_L1") (pintype "power_in"))
      (node (ref "IC33") (pin "L17") (pinfunction "GND_L17") (pintype "power_in"))
      (node (ref "IC33") (pin "L27") (pinfunction "GND_L27") (pintype "power_in"))
      (node (ref "IC33") (pin "L5") (pinfunction "GND_L5") (pintype "power_in"))
      (node (ref "IC33") (pin "L7") (pinfunction "GND_L7") (pintype "power_in"))
      (node (ref "IC33") (pin "M14") (pinfunction "GND_M14") (pintype "power_in"))
      (node (ref "IC33") (pin "M20") (pinfunction "GND_M20") (pintype "power_in"))
      (node (ref "IC33") (pin "M24") (pinfunction "GND_M24") (pintype "power_in"))
      (node (ref "IC33") (pin "M34") (pinfunction "GND_M34") (pintype "power_in"))
      (node (ref "IC33") (pin "M4") (pinfunction "GND_M4") (pintype "power_in"))
      (node (ref "IC33") (pin "M7") (pinfunction "GND_M7") (pintype "power_in"))
      (node (ref "IC33") (pin "N1") (pinfunction "GND_N1") (pintype "power_in"))
      (node (ref "IC33") (pin "N11") (pinfunction "GND_N11") (pintype "power_in"))
      (node (ref "IC33") (pin "N13") (pinfunction "GND_N13") (pintype "power_in"))
      (node (ref "IC33") (pin "N15") (pinfunction "GND_N15") (pintype "power_in"))
      (node (ref "IC33") (pin "N17") (pinfunction "GND_N17") (pintype "power_in"))
      (node (ref "IC33") (pin "N19") (pinfunction "GND_N19") (pintype "power_in"))
      (node (ref "IC33") (pin "N2") (pinfunction "GND_N2") (pintype "power_in"))
      (node (ref "IC33") (pin "N21") (pinfunction "GND_N21") (pintype "power_in"))
      (node (ref "IC33") (pin "N31") (pinfunction "GND_N31") (pintype "power_in"))
      (node (ref "IC33") (pin "N5") (pinfunction "GND_N5") (pintype "power_in"))
      (node (ref "IC33") (pin "N7") (pinfunction "GND_N7") (pintype "power_in"))
      (node (ref "IC33") (pin "N8") (pinfunction "VBATT_0_N8") (pintype "power_in"))
      (node (ref "IC33") (pin "N9") (pinfunction "GND_N9") (pintype "power_in"))
      (node (ref "IC33") (pin "P10") (pinfunction "GND_P10") (pintype "power_in"))
      (node (ref "IC33") (pin "P12") (pinfunction "GND_P12") (pintype "power_in"))
      (node (ref "IC33") (pin "P14") (pinfunction "GND_P14") (pintype "power_in"))
      (node (ref "IC33") (pin "P16") (pinfunction "GND_P16") (pintype "power_in"))
      (node (ref "IC33") (pin "P18") (pinfunction "GND_P18") (pintype "power_in"))
      (node (ref "IC33") (pin "P20") (pinfunction "GND_P20") (pintype "power_in"))
      (node (ref "IC33") (pin "P22") (pinfunction "GND_P22") (pintype "power_in"))
      (node (ref "IC33") (pin "P28") (pinfunction "GND_P28") (pintype "power_in"))
      (node (ref "IC33") (pin "P3") (pinfunction "GND_P3") (pintype "power_in"))
      (node (ref "IC33") (pin "P4") (pinfunction "GND_P4") (pintype "power_in"))
      (node (ref "IC33") (pin "P7") (pinfunction "GND_P7") (pintype "power_in"))
      (node (ref "IC33") (pin "R1") (pinfunction "GND_R1") (pintype "power_in"))
      (node (ref "IC33") (pin "R11") (pinfunction "GND_R11") (pintype "power_in"))
      (node (ref "IC33") (pin "R13") (pinfunction "GND_R13") (pintype "power_in"))
      (node (ref "IC33") (pin "R15") (pinfunction "GND_R15") (pintype "power_in"))
      (node (ref "IC33") (pin "R17") (pinfunction "GND_R17") (pintype "power_in"))
      (node (ref "IC33") (pin "R19") (pinfunction "GND_R19") (pintype "power_in"))
      (node (ref "IC33") (pin "R21") (pinfunction "GND_R21") (pintype "power_in"))
      (node (ref "IC33") (pin "R23") (pinfunction "GND_R23") (pintype "power_in"))
      (node (ref "IC33") (pin "R25") (pinfunction "GND_R25") (pintype "power_in"))
      (node (ref "IC33") (pin "R5") (pinfunction "GND_R5") (pintype "power_in"))
      (node (ref "IC33") (pin "R7") (pinfunction "GND_R7") (pintype "power_in"))
      (node (ref "IC33") (pin "R9") (pinfunction "GND_R9") (pintype "power_in"))
      (node (ref "IC33") (pin "T10") (pinfunction "GND_T10") (pintype "power_in"))
      (node (ref "IC33") (pin "T12") (pinfunction "GND_T12") (pintype "power_in"))
      (node (ref "IC33") (pin "T14") (pinfunction "GND_T14") (pintype "power_in"))
      (node (ref "IC33") (pin "T16") (pinfunction "GND_T16") (pintype "power_in"))
      (node (ref "IC33") (pin "T20") (pinfunction "GND_T20") (pintype "power_in"))
      (node (ref "IC33") (pin "T22") (pinfunction "GND_T22") (pintype "power_in"))
      (node (ref "IC33") (pin "T32") (pinfunction "GND_T32") (pintype "power_in"))
      (node (ref "IC33") (pin "T4") (pinfunction "GND_T4") (pintype "power_in"))
      (node (ref "IC33") (pin "T7") (pinfunction "GND_T7") (pintype "power_in"))
      (node (ref "IC33") (pin "T8") (pinfunction "GND_T8") (pintype "power_in"))
      (node (ref "IC33") (pin "U1") (pinfunction "GND_U1") (pintype "power_in"))
      (node (ref "IC33") (pin "U11") (pinfunction "GND_U11") (pintype "power_in"))
      (node (ref "IC33") (pin "U13") (pinfunction "GND_U13") (pintype "power_in"))
      (node (ref "IC33") (pin "U15") (pinfunction "GND_U15") (pintype "power_in"))
      (node (ref "IC33") (pin "U19") (pinfunction "GND_U19") (pintype "power_in"))
      (node (ref "IC33") (pin "U2") (pinfunction "GND_U2") (pintype "power_in"))
      (node (ref "IC33") (pin "U21") (pinfunction "GND_U21") (pintype "power_in"))
      (node (ref "IC33") (pin "U29") (pinfunction "GND_U29") (pintype "power_in"))
      (node (ref "IC33") (pin "U5") (pinfunction "GND_U5") (pintype "power_in"))
      (node (ref "IC33") (pin "U7") (pinfunction "GND_U7") (pintype "power_in"))
      (node (ref "IC33") (pin "U9") (pinfunction "GND_U9") (pintype "power_in"))
      (node (ref "IC33") (pin "V10") (pinfunction "GND_V10") (pintype "power_in"))
      (node (ref "IC33") (pin "V12") (pinfunction "GND_V12") (pintype "power_in"))
      (node (ref "IC33") (pin "V14") (pinfunction "GND_V14") (pintype "power_in"))
      (node (ref "IC33") (pin "V16") (pinfunction "GND_V16") (pintype "power_in"))
      (node (ref "IC33") (pin "V20") (pinfunction "GND_V20") (pintype "power_in"))
      (node (ref "IC33") (pin "V22") (pinfunction "GND_V22") (pintype "power_in"))
      (node (ref "IC33") (pin "V26") (pinfunction "GND_V26") (pintype "power_in"))
      (node (ref "IC33") (pin "V3") (pinfunction "GND_V3") (pintype "power_in"))
      (node (ref "IC33") (pin "V4") (pinfunction "GND_V4") (pintype "power_in"))
      (node (ref "IC33") (pin "V7") (pinfunction "GND_V7") (pintype "power_in"))
      (node (ref "IC33") (pin "W1") (pinfunction "GND_W1") (pintype "power_in"))
      (node (ref "IC33") (pin "W11") (pinfunction "GND_W11") (pintype "power_in"))
      (node (ref "IC33") (pin "W13") (pinfunction "GND_W13") (pintype "power_in"))
      (node (ref "IC33") (pin "W15") (pinfunction "GND_W15") (pintype "power_in"))
      (node (ref "IC33") (pin "W19") (pinfunction "GND_W19") (pintype "power_in"))
      (node (ref "IC33") (pin "W21") (pinfunction "GND_W21") (pintype "power_in"))
      (node (ref "IC33") (pin "W23") (pinfunction "GND_W23") (pintype "power_in"))
      (node (ref "IC33") (pin "W33") (pinfunction "GND_W33") (pintype "power_in"))
      (node (ref "IC33") (pin "W5") (pinfunction "GND_W5") (pintype "power_in"))
      (node (ref "IC33") (pin "W7") (pinfunction "GND_W7") (pintype "power_in"))
      (node (ref "IC33") (pin "W9") (pinfunction "GND_W9") (pintype "power_in"))
      (node (ref "IC33") (pin "Y10") (pinfunction "GND_Y10") (pintype "power_in"))
      (node (ref "IC33") (pin "Y12") (pinfunction "GND_Y12") (pintype "power_in"))
      (node (ref "IC33") (pin "Y14") (pinfunction "GND_Y14") (pintype "power_in"))
      (node (ref "IC33") (pin "Y16") (pinfunction "GND_Y16") (pintype "power_in"))
      (node (ref "IC33") (pin "Y18") (pinfunction "GND_Y18") (pintype "power_in"))
      (node (ref "IC33") (pin "Y20") (pinfunction "GND_Y20") (pintype "power_in"))
      (node (ref "IC33") (pin "Y22") (pinfunction "GND_Y22") (pintype "power_in"))
      (node (ref "IC33") (pin "Y30") (pinfunction "GND_Y30") (pintype "power_in"))
      (node (ref "IC33") (pin "Y4") (pinfunction "GND_Y4") (pintype "power_in"))
      (node (ref "IC33") (pin "Y5") (pinfunction "GND_Y5") (pintype "power_in"))
      (node (ref "IC33") (pin "Y6") (pinfunction "GND_Y6") (pintype "power_in"))
      (node (ref "IC33") (pin "Y7") (pinfunction "GND_Y7") (pintype "power_in"))
      (node (ref "IC33") (pin "Y8") (pinfunction "VFS_0_Y8") (pintype "power_in"))
      (node (ref "L4") (pin "1") (pinfunction "1_1") (pintype "passive"))
    )
  )
)
